# design.net
KiCad netlist of a schematic drawn in Altium Designer
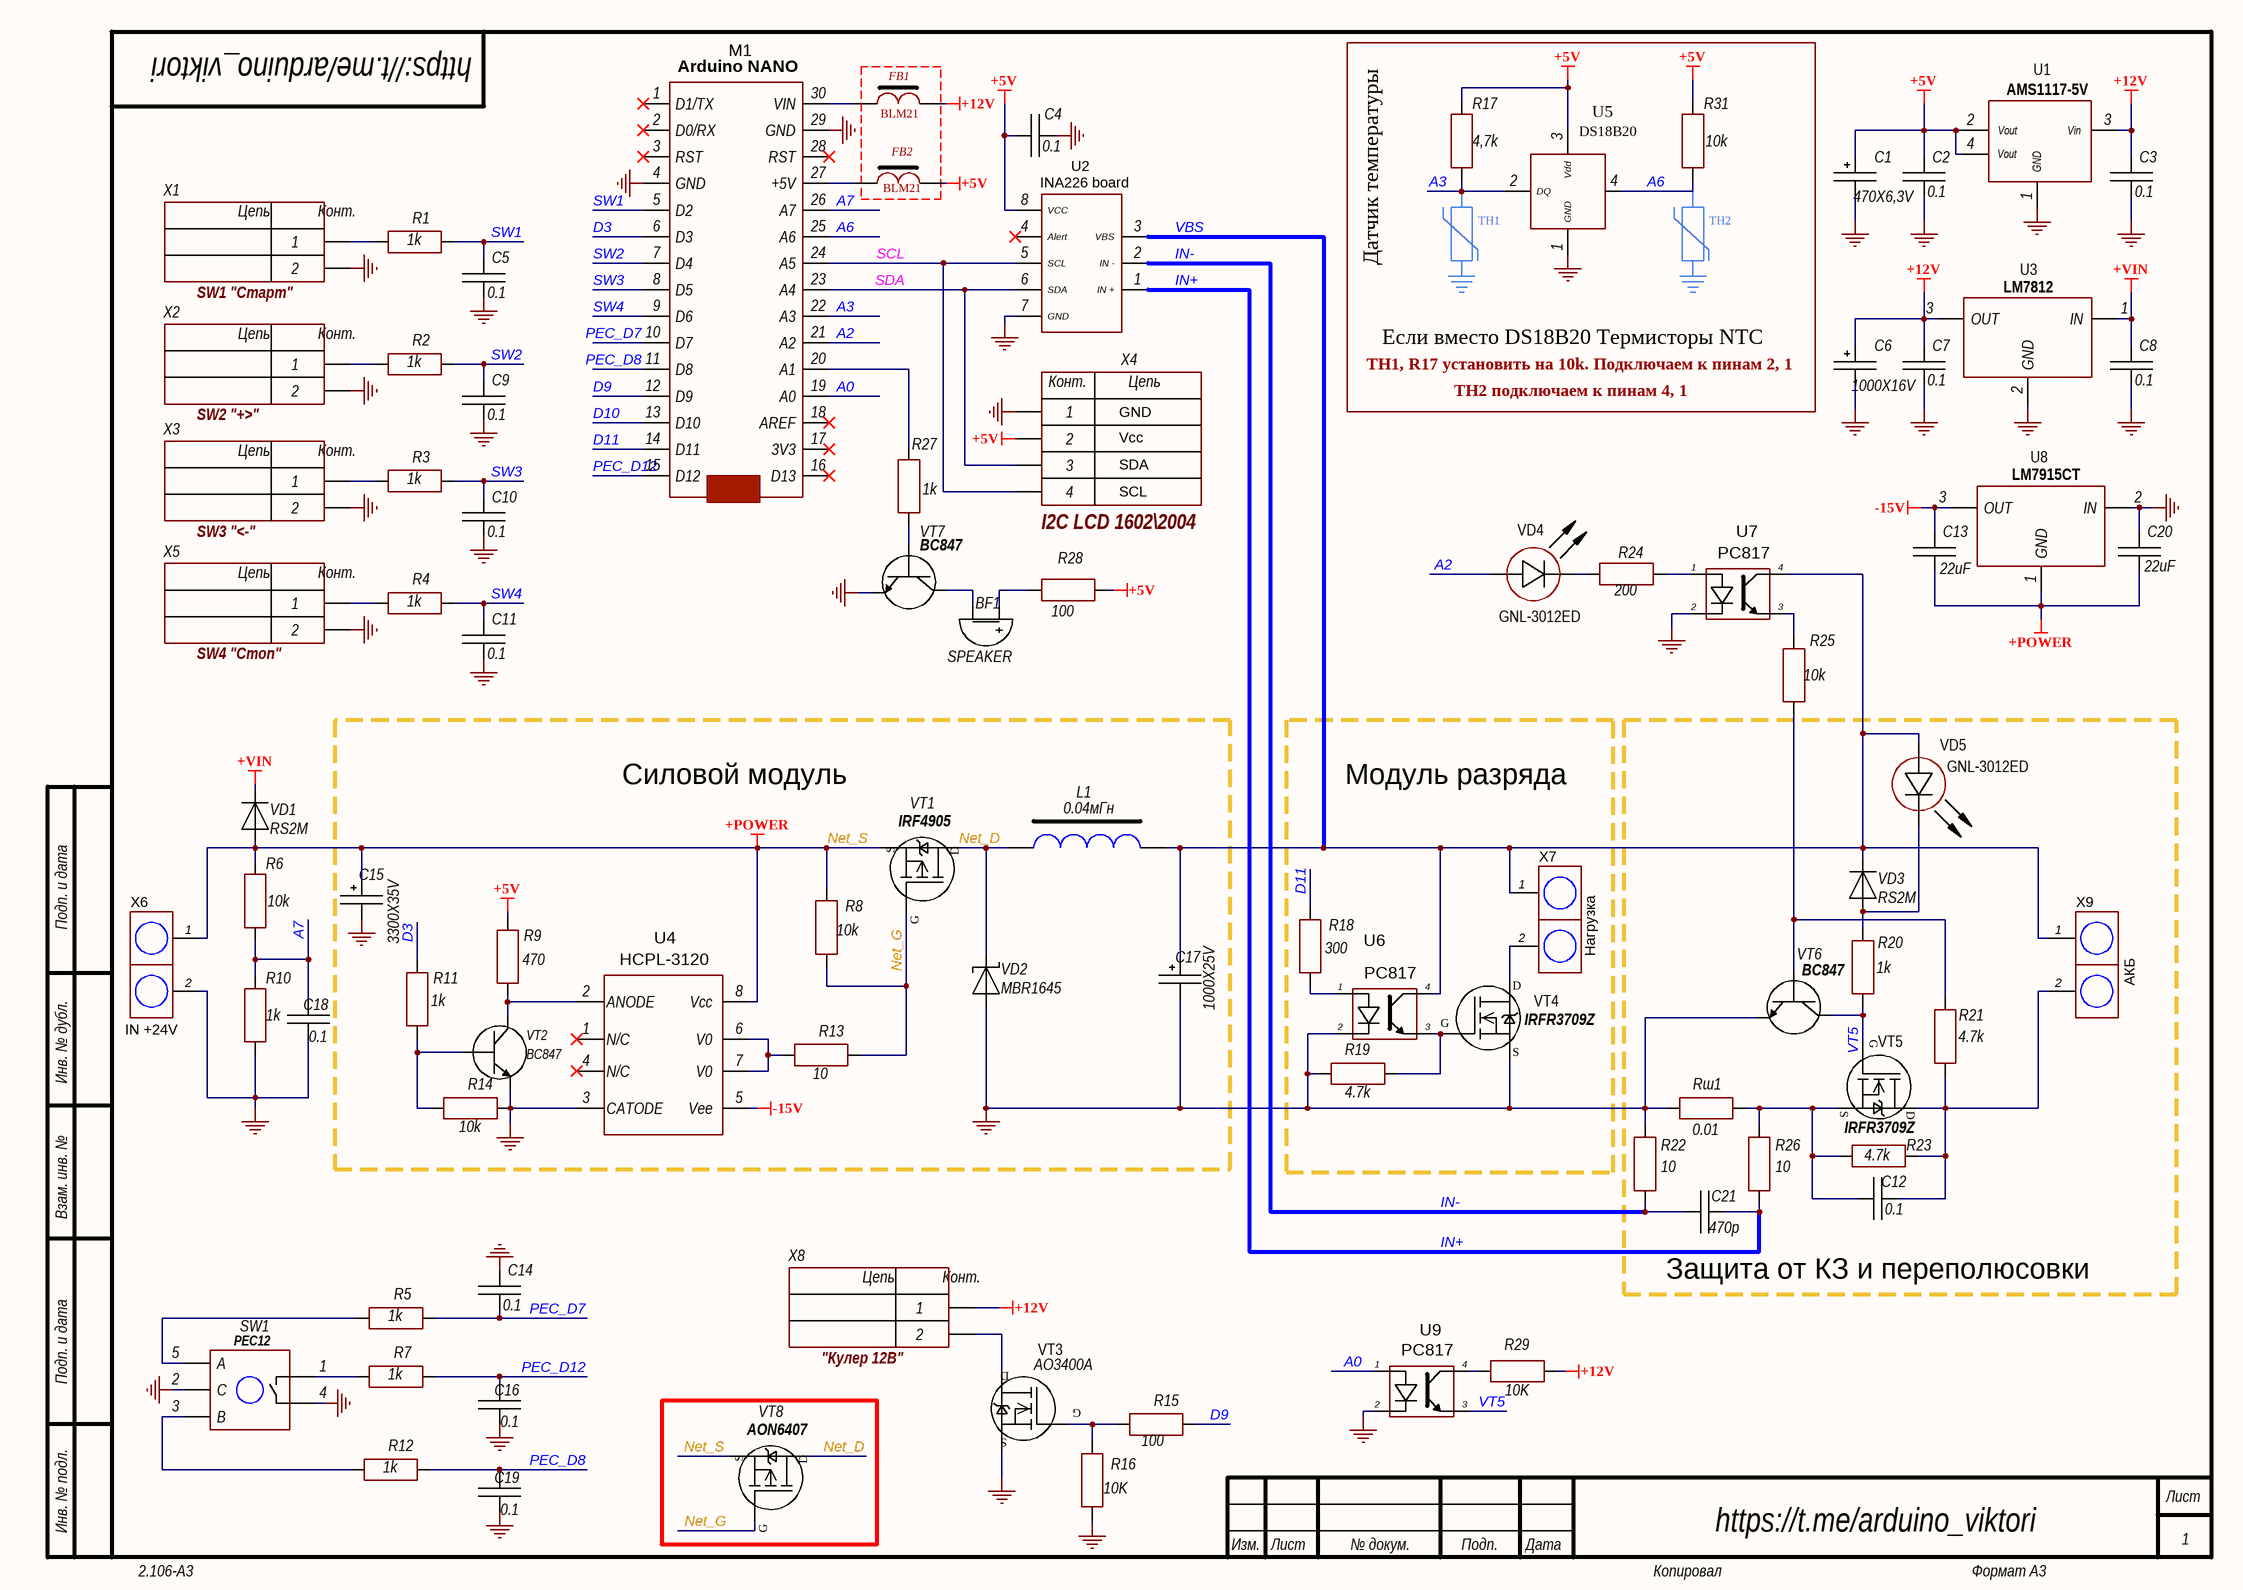
[diagram p0: Схема ЗУ.SchDoc]

(export (version "E")
  (design (tool "Eeschema 10.0.6"))
  (components
    (comp (ref "BF1")
      (value "SPEAKER")
      (footprint "CON: CWF-2")
      (fields (field (name "MANUFACTURER") "PUI Audio, Inc."))
      (libsource (lib "Discrete") (part "Buzzer"))
    )
    (comp (ref "C1")
      (value "470X6,3V")
      (footprint "standard:D8C3.5H12")
      (libsource (lib "Discrete") (part "AlumCap"))
    )
    (comp (ref "C2")
      (value "0.1")
      (footprint "standard:CH0805C")
      (libsource (lib "Discrete") (part "Capacitor"))
    )
    (comp (ref "C3")
      (value "0.1")
      (footprint "standard:CH0805C")
      (libsource (lib "Discrete") (part "Capacitor"))
    )
    (comp (ref "C4")
      (value "0.1")
      (footprint "standard:CH0805C")
      (libsource (lib "Discrete") (part "Capacitor"))
    )
    (comp (ref "C5")
      (value "0.1")
      (footprint "standard:CH0805C")
      (libsource (lib "Discrete") (part "Capacitor"))
    )
    (comp (ref "C6")
      (value "1000X16V")
      (footprint "standard:D10C5H20")
      (libsource (lib "Discrete") (part "AlumCap"))
    )
    (comp (ref "C7")
      (value "0.1")
      (footprint "standard:CH0805C")
      (libsource (lib "Discrete") (part "Capacitor"))
    )
    (comp (ref "C8")
      (value "0.1")
      (footprint "standard:CH0805C")
      (libsource (lib "Discrete") (part "Capacitor"))
    )
    (comp (ref "C9")
      (value "0.1")
      (footprint "standard:CH0805C")
      (libsource (lib "Discrete") (part "Capacitor"))
    )
    (comp (ref "C10")
      (value "0.1")
      (footprint "standard:CH0805C")
      (libsource (lib "Discrete") (part "Capacitor"))
    )
    (comp (ref "C11")
      (value "0.1")
      (footprint "standard:CH0805C")
      (libsource (lib "Discrete") (part "Capacitor"))
    )
    (comp (ref "C12")
      (value "0.1")
      (footprint "standard:CH0805C")
      (libsource (lib "Discrete") (part "Capacitor"))
    )
    (comp (ref "C13")
      (value "22uF")
      (footprint "standard:CH1206C")
      (libsource (lib "Discrete") (part "Capacitor"))
    )
    (comp (ref "C14")
      (value "0.1")
      (footprint "standard:CH0805C")
      (libsource (lib "Discrete") (part "Capacitor"))
    )
    (comp (ref "C15")
      (value "3300X35V")
      (footprint "standard:D16C7.5H25")
      (libsource (lib "Discrete") (part "AlumCap"))
    )
    (comp (ref "C16")
      (value "0.1")
      (footprint "standard:CH0805C")
      (libsource (lib "Discrete") (part "Capacitor"))
    )
    (comp (ref "C17")
      (value "1000X25V")
      (footprint "standard:D10C5H20")
      (libsource (lib "Discrete") (part "AlumCap"))
    )
    (comp (ref "C18")
      (value "0.1")
      (footprint "standard:CH0805C")
      (libsource (lib "Discrete") (part "Capacitor"))
    )
    (comp (ref "C19")
      (value "0.1")
      (footprint "standard:CH0805C")
      (libsource (lib "Discrete") (part "Capacitor"))
    )
    (comp (ref "C20")
      (value "22uF")
      (footprint "standard:CH1206C")
      (libsource (lib "Discrete") (part "Capacitor"))
    )
    (comp (ref "C21")
      (value "470p")
      (footprint "standard:CH0805C")
      (libsource (lib "Discrete") (part "Capacitor"))
    )
    (comp (ref "FB1") (value "BLM21") (footprint "CH0805L") (libsource (lib "Discrete") (part "FB-1")))
    (comp (ref "FB2") (value "BLM21") (footprint "CH0805L") (libsource (lib "Discrete") (part "FB-1")))
    (comp (ref "L1") (value "0.04мГн") (footprint "POWER_L") (libsource (lib "Transformers") (part "TRANS")))
    (comp (ref "M1")
      (value "Arduino NANO")
      (footprint "ARDUINO NANA")
      (libsource (lib "Module") (part "Arduino nano"))
    )
    (comp (ref "R1") (value "1k") (footprint "standard:CH0805R") (libsource (lib "") (part "Resistor_2")))
    (comp (ref "R2") (value "1k") (footprint "standard:CH0805R") (libsource (lib "") (part "Resistor_2")))
    (comp (ref "R3") (value "1k") (footprint "standard:CH0805R") (libsource (lib "") (part "Resistor_2")))
    (comp (ref "R4") (value "1k") (footprint "standard:CH0805R") (libsource (lib "") (part "Resistor_2")))
    (comp (ref "R5") (value "1k") (footprint "standard:CH0805R") (libsource (lib "") (part "Resistor_2")))
    (comp (ref "R6")
      (value "10k")
      (footprint "standard:CH0805R")
      (libsource (lib "Discrete") (part "Resistor"))
    )
    (comp (ref "R7") (value "1k") (footprint "standard:CH0805R") (libsource (lib "") (part "Resistor_2")))
    (comp (ref "R8")
      (value "10k")
      (footprint "standard:CH0805R")
      (libsource (lib "Discrete") (part "Resistor"))
    )
    (comp (ref "R9")
      (value "470")
      (footprint "standard:CH0805R")
      (libsource (lib "Discrete") (part "Resistor"))
    )
    (comp (ref "R10")
      (value "1k")
      (footprint "standard:CH0805R")
      (libsource (lib "Discrete") (part "Resistor"))
    )
    (comp (ref "R11")
      (value "1k")
      (footprint "standard:CH0805R")
      (libsource (lib "Discrete") (part "Resistor"))
    )
    (comp (ref "R12") (value "1k") (footprint "standard:CH0805R") (libsource (lib "") (part "Resistor_2")))
    (comp (ref "R13") (value "10") (footprint "standard:CH0805R") (libsource (lib "") (part "Resistor_2")))
    (comp (ref "R14") (value "10k") (footprint "standard:CH0805R") (libsource (lib "") (part "Resistor_2")))
    (comp (ref "R15") (value "100") (footprint "standard:CH0805R") (libsource (lib "") (part "Resistor_2")))
    (comp (ref "R16")
      (value "10K")
      (footprint "standard:CH0805R")
      (libsource (lib "Discrete") (part "Resistor"))
    )
    (comp (ref "R17")
      (value "4,7k")
      (footprint "standard:CH0805R")
      (libsource (lib "Discrete") (part "Resistor"))
    )
    (comp (ref "R18")
      (value "300")
      (footprint "standard:CH0805R")
      (libsource (lib "Discrete") (part "Resistor"))
    )
    (comp (ref "R19") (value "4.7k") (footprint "standard:CH0805R") (libsource (lib "") (part "Resistor_4")))
    (comp (ref "R20") (value "1k") (footprint "standard:CH0805R") (libsource (lib "") (part "Resistor_1")))
    (comp (ref "R21") (value "4.7k") (footprint "standard:CH0805R") (libsource (lib "") (part "Resistor_1")))
    (comp (ref "R22") (value "10") (footprint "standard:CH0805R") (libsource (lib "") (part "Resistor_1")))
    (comp (ref "R23") (value "4.7k") (footprint "standard:CH0805R") (libsource (lib "") (part "Resistor_3")))
    (comp (ref "R24") (value "200") (footprint "standard:CH0805R") (libsource (lib "") (part "Resistor_2")))
    (comp (ref "R25") (value "10k") (footprint "standard:CH0805R") (libsource (lib "") (part "Resistor_1")))
    (comp (ref "R26") (value "10") (footprint "standard:CH0805R") (libsource (lib "") (part "Resistor_1")))
    (comp (ref "R27")
      (value "1k")
      (footprint "standard:CH0805R")
      (libsource (lib "Discrete") (part "Resistor"))
    )
    (comp (ref "R28") (value "100") (footprint "standard:CH0805R") (libsource (lib "") (part "Resistor_3")))
    (comp (ref "R29") (value "10K") (footprint "standard:CH0805R") (libsource (lib "") (part "Resistor_3")))
    (comp (ref "R31")
      (value "10k")
      (footprint "standard:CH0805R")
      (libsource (lib "Discrete") (part "Resistor"))
    )
    (comp (ref "Rш1") (value "0.01") (footprint "HUNT 10mm") (libsource (lib "") (part "Resistor_3")))
    (comp (ref "SW1")
      (value "PEC12")
      (footprint "CON: CWF-5")
      (description "Encoder")
      (libsource (lib "Connectors") (part "PEC12"))
    )
    (comp (ref "U1") (value "AMS1117-5V") (footprint "SOT223") (libsource (lib "Analog") (part "AMS117")))
    (comp (ref "U2")
      (value "INA226 board")
      (footprint "CON: PBS-8")
      (libsource (lib "Module") (part "INA226"))
    )
    (comp (ref "U3")
      (value "LM7812")
      (footprint "TO220_123")
      (libsource (lib "Power Supplies") (part "7809"))
    )
    (comp (ref "U4") (value "HCPL-3120") (footprint "DIP-8") (libsource (lib "Digital") (part "HCPL-3120")))
    (comp (ref "U5")
      (value "DS18B20")
      (footprint "CON: PLS-4")
      (libsource (lib "Module") (part "DS18B20_V1"))
    )
    (comp (ref "U6") (value "PC817") (footprint "PC817-SMD") (libsource (lib "") (part "PC817_1")))
    (comp (ref "U7") (value "PC817") (footprint "PC817-SMD") (libsource (lib "Discrete") (part "PC817")))
    (comp (ref "U8") (value "LM7915CT") (footprint "TO-220_90") (libsource (lib "") (part "7809_1")))
    (comp (ref "U9") (value "PC817") (footprint "PC817-SMD") (libsource (lib "Discrete") (part "PC817")))
    (comp (ref "VD1") (value "RS2M") (footprint "standard:SMB") (libsource (lib "Diods") (part "Diod")))
    (comp (ref "VD2")
      (value "MBR1645")
      (footprint "TO-220_2pin")
      (libsource (lib "Diods") (part "Diod Schottky"))
    )
    (comp (ref "VD3") (value "RS2M") (footprint "standard:SMB") (libsource (lib "Diods") (part "Diod")))
    (comp (ref "VD4")
      (value "GNL-3012ED")
      (footprint "DIOD: LED5MM_R")
      (libsource (lib "Diods") (part "LED"))
    )
    (comp (ref "VD5")
      (value "GNL-3012ED")
      (footprint "DIOD: LED5MM_R")
      (libsource (lib "Diods") (part "LED"))
    )
    (comp (ref "VT1")
      (value "IRF4905")
      (footprint "TO220_123_V")
      (libsource (lib "Transistor") (part "P-KANAL"))
    )
    (comp (ref "VT2") (value "BC847") (footprint "SOT23_123") (libsource (lib "Transistor") (part "N-P-N")))
    (comp (ref "VT3") (value "AO3400A") (footprint "SOT23_132") (libsource (lib "") (part "N-KANAL_1")))
    (comp (ref "VT4") (value "IRFR3709Z") (footprint "D2PAK") (libsource (lib "Transistor") (part "N-KANAL")))
    (comp (ref "VT5") (value "IRFR3709Z") (footprint "D2PAK") (libsource (lib "Transistor") (part "N-KANAL")))
    (comp (ref "VT6") (value "BC847") (footprint "SOT23_123") (libsource (lib "Transistor") (part "N-P-N")))
    (comp (ref "VT7") (value "BC847") (footprint "SOT23_123") (libsource (lib "Transistor") (part "N-P-N")))
    (comp (ref "VT8") (value "AON6407") (footprint "DFN5x6") (libsource (lib "Transistor") (part "P-KANAL")))
    (comp (ref "X1")
      (value "SW1 \"Старт\"")
      (footprint "custom:CON: CWF-2")
      (libsource (lib "Connectors") (part "2-Connector"))
    )
    (comp (ref "X2")
      (value "SW2 \"+>\"")
      (footprint "custom:CON: CWF-2")
      (libsource (lib "Connectors") (part "2-Connector"))
    )
    (comp (ref "X3")
      (value "SW3 \"<-\"")
      (footprint "custom:CON: CWF-2")
      (libsource (lib "Connectors") (part "2-Connector"))
    )
    (comp (ref "X4")
      (value "I2C LCD 160~{2}2004")
      (footprint "custom:CON: CWF-4")
      (libsource (lib "Connectors") (part "4-Connector"))
    )
    (comp (ref "X5")
      (value "SW4 \"Стоп\"")
      (footprint "custom:CON: CWF-2")
      (libsource (lib "Connectors") (part "2-Connector"))
    )
    (comp (ref "X6")
      (value "IN +24V")
      (footprint "CON: 2P_5mm")
      (libsource (lib "Connectors") (part "2-CON"))
    )
    (comp (ref "X7") (value "Нагрузка") (footprint "CON: 2P_5mm") (libsource (lib "") (part "2-CON_1")))
    (comp (ref "X8")
      (value "\"Кулер 12В\"")
      (footprint "custom:CON: CWF-2")
      (libsource (lib "Connectors") (part "2-Connector"))
    )
    (comp (ref "X9") (value "АКБ") (footprint "CON: 2P_5mm") (libsource (lib "") (part "2-CON_1")))
  )
  (nets
    (net (code "1") (name "+5V") (class "Default")
      (node (ref "C1") (pin "1") (pinfunction "1_1") (pintype "power_in"))
      (node (ref "C2") (pin "1") (pinfunction "1_1") (pintype "passive"))
      (node (ref "C4") (pin "2") (pinfunction "2_2") (pintype "passive"))
      (node (ref "FB2") (pin "2") (pinfunction "2_2") (pintype "passive"))
      (node (ref "R17") (pin "2") (pinfunction "2_2") (pintype "passive"))
      (node (ref "R28") (pin "1") (pinfunction "1_1") (pintype "passive"))
      (node (ref "R31") (pin "2") (pinfunction "2_2") (pintype "passive"))
      (node (ref "R9") (pin "2") (pinfunction "2_2") (pintype "passive"))
      (node (ref "U1") (pin "2") (pinfunction "Vout_2") (pintype "passive"))
      (node (ref "U1") (pin "4") (pinfunction "Vout_4") (pintype "passive"))
      (node (ref "U2") (pin "8") (pinfunction "VCC_8") (pintype "passive"))
      (node (ref "U5") (pin "3") (pinfunction "Vdd_3") (pintype "passive"))
      (node (ref "X4") (pin "2") (pinfunction "2_2") (pintype "passive"))
    )
    (net (code "2") (name "+12V") (class "Default")
      (node (ref "C3") (pin "1") (pinfunction "1_1") (pintype "passive"))
      (node (ref "C6") (pin "1") (pinfunction "1_1") (pintype "power_in"))
      (node (ref "C7") (pin "1") (pinfunction "1_1") (pintype "passive"))
      (node (ref "FB1") (pin "2") (pinfunction "2_2") (pintype "passive"))
      (node (ref "R29") (pin "1") (pinfunction "1_1") (pintype "passive"))
      (node (ref "U1") (pin "3") (pinfunction "Vin_3") (pintype "passive"))
      (node (ref "U3") (pin "3") (pinfunction "OUT_3") (pintype "passive"))
      (node (ref "X8") (pin "1") (pinfunction "1_1") (pintype "passive"))
    )
    (net (code "3") (name "+POWER") (class "Default")
      (node (ref "C13") (pin "2") (pinfunction "2_2") (pintype "passive"))
      (node (ref "C15") (pin "1") (pinfunction "1_1") (pintype "power_in"))
      (node (ref "C20") (pin "2") (pinfunction "2_2") (pintype "passive"))
      (node (ref "R6") (pin "2") (pinfunction "2_2") (pintype "passive"))
      (node (ref "R8") (pin "2") (pinfunction "2_2") (pintype "passive"))
      (node (ref "U4") (pin "8") (pinfunction "Vcc_8") (pintype "passive"))
      (node (ref "U8") (pin "1") (pinfunction "GND_1") (pintype "passive"))
      (node (ref "VD1") (pin "1") (pinfunction "1_1") (pintype "passive"))
      (node (ref "VT1") (pin "3") (pinfunction "Исток_3") (pintype "passive"))
      (node (ref "VT8") (pin "3") (pinfunction "Исток_3") (pintype "passive"))
      (node (ref "X6") (pin "1") (pinfunction "1_1") (pintype "passive"))
    )
    (net (code "4") (name "+VIN") (class "Default")
      (node (ref "C8") (pin "1") (pinfunction "1_1") (pintype "passive"))
      (node (ref "U3") (pin "1") (pinfunction "IN_1") (pintype "power_in"))
      (node (ref "VD1") (pin "2") (pinfunction "2_2") (pintype "passive"))
    )
    (net (code "5") (name "-15V") (class "Default")
      (node (ref "C13") (pin "1") (pinfunction "1_1") (pintype "passive"))
      (node (ref "U4") (pin "5") (pinfunction "Vee_5") (pintype "passive"))
      (node (ref "U8") (pin "3") (pinfunction "OUT_3") (pintype "passive"))
    )
    (net (code "6") (name "/A0") (class "Default")
      (node (ref "M1") (pin "19") (pinfunction "A0_19") (pintype "passive"))
      (node (ref "U9") (pin "1") (pinfunction "1_1") (pintype "passive"))
    )
    (net (code "7") (name "/A2") (class "Default")
      (node (ref "M1") (pin "21") (pinfunction "A2_21") (pintype "passive"))
      (node (ref "VD4") (pin "1") (pinfunction "A_1") (pintype "passive"))
    )
    (net (code "8") (name "/A3") (class "Default")
      (node (ref "M1") (pin "22") (pinfunction "A3_22") (pintype "passive"))
      (node (ref "R17") (pin "1") (pinfunction "1_1") (pintype "passive"))
      (node (ref "U5") (pin "2") (pinfunction "DQ_2") (pintype "passive"))
    )
    (net (code "9") (name "/A6") (class "Default")
      (node (ref "M1") (pin "25") (pinfunction "A6_25") (pintype "passive"))
      (node (ref "R31") (pin "1") (pinfunction "1_1") (pintype "passive"))
      (node (ref "U5") (pin "4") (pinfunction "DQ_4") (pintype "passive"))
    )
    (net (code "10") (name "/A7") (class "Default")
      (node (ref "C18") (pin "1") (pinfunction "1_1") (pintype "passive"))
      (node (ref "M1") (pin "26") (pinfunction "A7_26") (pintype "passive"))
      (node (ref "R10") (pin "2") (pinfunction "2_2") (pintype "passive"))
      (node (ref "R6") (pin "1") (pinfunction "1_1") (pintype "passive"))
    )
    (net (code "11") (name "/D3") (class "Default")
      (node (ref "M1") (pin "6") (pinfunction "D3_6") (pintype "passive"))
      (node (ref "R11") (pin "2") (pinfunction "2_2") (pintype "passive"))
    )
    (net (code "12") (name "/D9") (class "Default")
      (node (ref "M1") (pin "12") (pinfunction "D9_12") (pintype "passive"))
      (node (ref "R15") (pin "2") (pinfunction "2_2") (pintype "passive"))
    )
    (net (code "13") (name "/D10") (class "Default")
      (node (ref "M1") (pin "13") (pinfunction "D10_13") (pintype "passive"))
    )
    (net (code "14") (name "/D11") (class "Default")
      (node (ref "M1") (pin "14") (pinfunction "D11_14") (pintype "passive"))
      (node (ref "R18") (pin "2") (pinfunction "2_2") (pintype "passive"))
    )
    (net (code "15") (name "/IN+") (class "Default")
      (node (ref "C21") (pin "1") (pinfunction "1_1") (pintype "passive"))
      (node (ref "R26") (pin "2") (pinfunction "2_2") (pintype "passive"))
      (node (ref "U2") (pin "1") (pinfunction "IN_+_1") (pintype "passive"))
    )
    (net (code "16") (name "/IN-") (class "Default")
      (node (ref "C21") (pin "2") (pinfunction "2_2") (pintype "passive"))
      (node (ref "R22") (pin "2") (pinfunction "2_2") (pintype "passive"))
      (node (ref "U2") (pin "2") (pinfunction "IN_-_2") (pintype "passive"))
    )
    (net (code "17") (name "/Net_D") (class "Default")
      (node (ref "L1") (pin "1") (pinfunction "1_1") (pintype "power_in"))
      (node (ref "VD2") (pin "1") (pinfunction "1_1") (pintype "passive"))
      (node (ref "VT1") (pin "2") (pinfunction "Сток_2") (pintype "passive"))
      (node (ref "VT8") (pin "2") (pinfunction "Сток_2") (pintype "passive"))
    )
    (net (code "18") (name "/Net_G") (class "Default")
      (node (ref "R13") (pin "2") (pinfunction "2_2") (pintype "passive"))
      (node (ref "R8") (pin "1") (pinfunction "1_1") (pintype "passive"))
      (node (ref "VT1") (pin "1") (pinfunction "Затвор(Gate)_1") (pintype "passive"))
      (node (ref "VT8") (pin "1") (pinfunction "Затвор(Gate)_1") (pintype "passive"))
    )
    (net (code "19") (name "/PEC_D7") (class "Default")
      (node (ref "C14") (pin "1") (pinfunction "1_1") (pintype "passive"))
      (node (ref "M1") (pin "10") (pinfunction "D7_10") (pintype "passive"))
      (node (ref "R5") (pin "2") (pinfunction "2_2") (pintype "passive"))
    )
    (net (code "20") (name "/PEC_D8") (class "Default")
      (node (ref "C19") (pin "1") (pinfunction "1_1") (pintype "passive"))
      (node (ref "M1") (pin "11") (pinfunction "D8_11") (pintype "passive"))
      (node (ref "R12") (pin "2") (pinfunction "2_2") (pintype "passive"))
    )
    (net (code "21") (name "/PEC_D12") (class "Default")
      (node (ref "C16") (pin "1") (pinfunction "1_1") (pintype "passive"))
      (node (ref "M1") (pin "15") (pinfunction "D12_15") (pintype "passive"))
      (node (ref "R7") (pin "2") (pinfunction "2_2") (pintype "passive"))
    )
    (net (code "22") (name "/SCL") (class "Default")
      (node (ref "M1") (pin "24") (pinfunction "A5_24") (pintype "passive"))
      (node (ref "U2") (pin "5") (pinfunction "SCL_5") (pintype "passive"))
      (node (ref "X4") (pin "4") (pinfunction "4_4") (pintype "power_in"))
    )
    (net (code "23") (name "/SDA") (class "Default")
      (node (ref "M1") (pin "23") (pinfunction "A4_23") (pintype "passive"))
      (node (ref "U2") (pin "6") (pinfunction "SDA_6") (pintype "passive"))
      (node (ref "X4") (pin "3") (pinfunction "3_3") (pintype "power_in"))
    )
    (net (code "24") (name "/SW1") (class "Default")
      (node (ref "C5") (pin "2") (pinfunction "2_2") (pintype "passive"))
      (node (ref "M1") (pin "5") (pinfunction "D2_5") (pintype "passive"))
      (node (ref "R1") (pin "2") (pinfunction "2_2") (pintype "passive"))
    )
    (net (code "25") (name "/SW2") (class "Default")
      (node (ref "C9") (pin "2") (pinfunction "2_2") (pintype "passive"))
      (node (ref "M1") (pin "7") (pinfunction "D4_7") (pintype "passive"))
      (node (ref "R2") (pin "2") (pinfunction "2_2") (pintype "passive"))
    )
    (net (code "26") (name "/SW3") (class "Default")
      (node (ref "C10") (pin "2") (pinfunction "2_2") (pintype "passive"))
      (node (ref "M1") (pin "8") (pinfunction "D5_8") (pintype "passive"))
      (node (ref "R3") (pin "2") (pinfunction "2_2") (pintype "passive"))
    )
    (net (code "27") (name "/SW4") (class "Default")
      (node (ref "C11") (pin "2") (pinfunction "2_2") (pintype "passive"))
      (node (ref "M1") (pin "9") (pinfunction "D6_9") (pintype "passive"))
      (node (ref "R4") (pin "2") (pinfunction "2_2") (pintype "passive"))
    )
    (net (code "28") (name "/VBS") (class "Default")
      (node (ref "C17") (pin "1") (pinfunction "1_1") (pintype "power_in"))
      (node (ref "L1") (pin "2") (pinfunction "2_2") (pintype "power_in"))
      (node (ref "U2") (pin "3") (pinfunction "VBS_3") (pintype "passive"))
      (node (ref "U6") (pin "4") (pinfunction "4_4") (pintype "passive"))
      (node (ref "U7") (pin "4") (pinfunction "4_4") (pintype "passive"))
      (node (ref "VD3") (pin "2") (pinfunction "2_2") (pintype "passive"))
      (node (ref "VD5") (pin "1") (pinfunction "A_1") (pintype "passive"))
      (node (ref "X7") (pin "1") (pinfunction "1_1") (pintype "passive"))
      (node (ref "X9") (pin "1") (pinfunction "1_1") (pintype "passive"))
    )
    (net (code "29") (name "/VT5") (class "Default")
      (node (ref "R20") (pin "2") (pinfunction "2_2") (pintype "passive"))
      (node (ref "U9") (pin "3") (pinfunction "3_3") (pintype "passive"))
      (node (ref "VT5") (pin "1") (pinfunction "Затвор_1") (pintype "passive"))
      (node (ref "VT6") (pin "2") (pinfunction "C_2") (pintype "passive"))
    )
    (net (code "30") (name "GND") (class "Default")
      (node (ref "C1") (pin "2") (pinfunction "2_2") (pintype "power_in"))
      (node (ref "C10") (pin "1") (pinfunction "1_1") (pintype "passive"))
      (node (ref "C11") (pin "1") (pinfunction "1_1") (pintype "passive"))
      (node (ref "C14") (pin "2") (pinfunction "2_2") (pintype "passive"))
      (node (ref "C15") (pin "2") (pinfunction "2_2") (pintype "power_in"))
      (node (ref "C16") (pin "2") (pinfunction "2_2") (pintype "passive"))
      (node (ref "C17") (pin "2") (pinfunction "2_2") (pintype "power_in"))
      (node (ref "C18") (pin "2") (pinfunction "2_2") (pintype "passive"))
      (node (ref "C19") (pin "2") (pinfunction "2_2") (pintype "passive"))
      (node (ref "C2") (pin "2") (pinfunction "2_2") (pintype "passive"))
      (node (ref "C20") (pin "1") (pinfunction "1_1") (pintype "passive"))
      (node (ref "C3") (pin "2") (pinfunction "2_2") (pintype "passive"))
      (node (ref "C4") (pin "1") (pinfunction "1_1") (pintype "passive"))
      (node (ref "C5") (pin "1") (pinfunction "1_1") (pintype "passive"))
      (node (ref "C6") (pin "2") (pinfunction "2_2") (pintype "power_in"))
      (node (ref "C7") (pin "2") (pinfunction "2_2") (pintype "passive"))
      (node (ref "C8") (pin "2") (pinfunction "2_2") (pintype "passive"))
      (node (ref "C9") (pin "1") (pinfunction "1_1") (pintype "passive"))
      (node (ref "M1") (pin "29") (pinfunction "GND_29") (pintype "passive"))
      (node (ref "M1") (pin "4") (pinfunction "GND_4") (pintype "passive"))
      (node (ref "R10") (pin "1") (pinfunction "1_1") (pintype "passive"))
      (node (ref "R14") (pin "2") (pinfunction "2_2") (pintype "passive"))
      (node (ref "R16") (pin "1") (pinfunction "1_1") (pintype "passive"))
      (node (ref "R19") (pin "2") (pinfunction "2_2") (pintype "passive"))
      (node (ref "R22") (pin "1") (pinfunction "1_1") (pintype "passive"))
      (node (ref "Rш1") (pin "2") (pinfunction "2_2") (pintype "passive"))
      (node (ref "SW1") (pin "2") (pinfunction "C_2") (pintype "passive"))
      (node (ref "SW1") (pin "4") (pinfunction "4_4") (pintype "passive"))
      (node (ref "U1") (pin "1") (pinfunction "GND_1") (pintype "passive"))
      (node (ref "U2") (pin "7") (pinfunction "GND_7") (pintype "passive"))
      (node (ref "U3") (pin "2") (pinfunction "GND_2") (pintype "passive"))
      (node (ref "U4") (pin "3") (pinfunction "CATODE_3") (pintype "passive"))
      (node (ref "U5") (pin "1") (pinfunction "GND_1") (pintype "passive"))
      (node (ref "U6") (pin "2") (pinfunction "2_2") (pintype "passive"))
      (node (ref "U7") (pin "2") (pinfunction "2_2") (pintype "passive"))
      (node (ref "U8") (pin "2") (pinfunction "IN_2") (pintype "power_in"))
      (node (ref "U9") (pin "2") (pinfunction "2_2") (pintype "passive"))
      (node (ref "VD2") (pin "2") (pinfunction "2_2") (pintype "passive"))
      (node (ref "VT2") (pin "3") (pinfunction "E_3") (pintype "passive"))
      (node (ref "VT3") (pin "2") (pinfunction "Исток_2") (pintype "passive"))
      (node (ref "VT4") (pin "3") (pinfunction "Исток_3") (pintype "passive"))
      (node (ref "VT6") (pin "3") (pinfunction "E_3") (pintype "passive"))
      (node (ref "VT7") (pin "3") (pinfunction "E_3") (pintype "passive"))
      (node (ref "X1") (pin "2") (pinfunction "2_2") (pintype "passive"))
      (node (ref "X2") (pin "2") (pinfunction "2_2") (pintype "passive"))
      (node (ref "X3") (pin "2") (pinfunction "2_2") (pintype "passive"))
      (node (ref "X4") (pin "1") (pinfunction "1_1") (pintype "passive"))
      (node (ref "X5") (pin "2") (pinfunction "2_2") (pintype "passive"))
      (node (ref "X6") (pin "2") (pinfunction "2_2") (pintype "passive"))
    )
    (net (code "31") (name "Net-(BF1-+)") (class "Default")
      (node (ref "BF1") (pin "1") (pinfunction "+_1") (pintype "passive"))
      (node (ref "R28") (pin "2") (pinfunction "2_2") (pintype "passive"))
    )
    (net (code "32") (name "Net-(BF1--)") (class "Default")
      (node (ref "BF1") (pin "2") (pinfunction "-_2") (pintype "passive"))
      (node (ref "VT7") (pin "2") (pinfunction "C_2") (pintype "passive"))
    )
    (net (code "33") (name "Net-(M1-+5V)") (class "Default")
      (node (ref "FB2") (pin "1") (pinfunction "1_1") (pintype "passive"))
      (node (ref "M1") (pin "27") (pinfunction "+5V_27") (pintype "passive"))
    )
    (net (code "34") (name "Net-(M1-A1)") (class "Default")
      (node (ref "M1") (pin "20") (pinfunction "A1_20") (pintype "passive"))
      (node (ref "R27") (pin "2") (pinfunction "2_2") (pintype "passive"))
    )
    (net (code "35") (name "Net-(M1-VIN)") (class "Default")
      (node (ref "FB1") (pin "1") (pinfunction "1_1") (pintype "passive"))
      (node (ref "M1") (pin "30") (pinfunction "VIN_30") (pintype "passive"))
    )
    (net (code "36") (name "Net-(R1-Pad1)") (class "Default")
      (node (ref "R1") (pin "1") (pinfunction "1_1") (pintype "passive"))
      (node (ref "X1") (pin "1") (pinfunction "1_1") (pintype "passive"))
    )
    (net (code "37") (name "Net-(R2-Pad1)") (class "Default")
      (node (ref "R2") (pin "1") (pinfunction "1_1") (pintype "passive"))
      (node (ref "X2") (pin "1") (pinfunction "1_1") (pintype "passive"))
    )
    (net (code "38") (name "Net-(R3-Pad1)") (class "Default")
      (node (ref "R3") (pin "1") (pinfunction "1_1") (pintype "passive"))
      (node (ref "X3") (pin "1") (pinfunction "1_1") (pintype "passive"))
    )
    (net (code "39") (name "Net-(R4-Pad1)") (class "Default")
      (node (ref "R4") (pin "1") (pinfunction "1_1") (pintype "passive"))
      (node (ref "X5") (pin "1") (pinfunction "1_1") (pintype "passive"))
    )
    (net (code "40") (name "Net-(R7-Pad1)") (class "Default")
      (node (ref "R7") (pin "1") (pinfunction "1_1") (pintype "passive"))
      (node (ref "SW1") (pin "1") (pinfunction "1_1") (pintype "passive"))
    )
    (net (code "41") (name "Net-(R13-Pad1)") (class "Default")
      (node (ref "R13") (pin "1") (pinfunction "1_1") (pintype "passive"))
      (node (ref "U4") (pin "6") (pinfunction "V0_6") (pintype "passive"))
      (node (ref "U4") (pin "7") (pinfunction "V0_7") (pintype "passive"))
    )
    (net (code "42") (name "Net-(R18-Pad1)") (class "Default")
      (node (ref "R18") (pin "1") (pinfunction "1_1") (pintype "passive"))
      (node (ref "U6") (pin "1") (pinfunction "1_1") (pintype "passive"))
    )
    (net (code "43") (name "Net-(R24-Pad2)") (class "Default")
      (node (ref "R24") (pin "2") (pinfunction "2_2") (pintype "passive"))
      (node (ref "U7") (pin "1") (pinfunction "1_1") (pintype "passive"))
    )
    (net (code "44") (name "Net-(R25-Pad1)") (class "Default")
      (node (ref "R25") (pin "1") (pinfunction "1_1") (pintype "passive"))
      (node (ref "U7") (pin "3") (pinfunction "3_3") (pintype "passive"))
    )
    (net (code "45") (name "Net-(R29-Pad2)") (class "Default")
      (node (ref "R29") (pin "2") (pinfunction "2_2") (pintype "passive"))
      (node (ref "U9") (pin "4") (pinfunction "4_4") (pintype "passive"))
    )
    (net (code "46") (name "Net-(SW1-A)") (class "Default")
      (node (ref "R5") (pin "1") (pinfunction "1_1") (pintype "passive"))
      (node (ref "SW1") (pin "5") (pinfunction "A_5") (pintype "passive"))
    )
    (net (code "47") (name "Net-(SW1-B)") (class "Default")
      (node (ref "R12") (pin "1") (pinfunction "1_1") (pintype "passive"))
      (node (ref "SW1") (pin "3") (pinfunction "B_3") (pintype "passive"))
    )
    (net (code "48") (name "Net-(U4-ANODE)") (class "Default")
      (node (ref "R9") (pin "1") (pinfunction "1_1") (pintype "passive"))
      (node (ref "U4") (pin "2") (pinfunction "ANODE_2") (pintype "passive"))
      (node (ref "VT2") (pin "2") (pinfunction "C_2") (pintype "passive"))
    )
    (net (code "49") (name "Net-(VD4-C)") (class "Default")
      (node (ref "R24") (pin "1") (pinfunction "1_1") (pintype "passive"))
      (node (ref "VD4") (pin "2") (pinfunction "C_2") (pintype "passive"))
    )
    (net (code "50") (name "Net-(VD5-C)") (class "Default")
      (node (ref "R20") (pin "1") (pinfunction "1_1") (pintype "passive"))
      (node (ref "VD3") (pin "1") (pinfunction "1_1") (pintype "passive"))
      (node (ref "VD5") (pin "2") (pinfunction "C_2") (pintype "passive"))
    )
    (net (code "51") (name "Net-(VT2-B)") (class "Default")
      (node (ref "R11") (pin "1") (pinfunction "1_1") (pintype "passive"))
      (node (ref "R14") (pin "1") (pinfunction "1_1") (pintype "passive"))
      (node (ref "VT2") (pin "1") (pinfunction "B_1") (pintype "passive"))
    )
    (net (code "52") (name "Net-(VT3-Затвор)") (class "Default")
      (node (ref "R15") (pin "1") (pinfunction "1_1") (pintype "passive"))
      (node (ref "R16") (pin "2") (pinfunction "2_2") (pintype "passive"))
      (node (ref "VT3") (pin "1") (pinfunction "Затвор_1") (pintype "passive"))
    )
    (net (code "53") (name "Net-(VT3-Сток)") (class "Default")
      (node (ref "VT3") (pin "3") (pinfunction "Сток_3") (pintype "passive"))
      (node (ref "X8") (pin "2") (pinfunction "2_2") (pintype "passive"))
    )
    (net (code "54") (name "Net-(VT4-Затвор)") (class "Default")
      (node (ref "R19") (pin "1") (pinfunction "1_1") (pintype "passive"))
      (node (ref "U6") (pin "3") (pinfunction "3_3") (pintype "passive"))
      (node (ref "VT4") (pin "1") (pinfunction "Затвор_1") (pintype "passive"))
    )
    (net (code "55") (name "Net-(VT4-Сток)") (class "Default")
      (node (ref "VT4") (pin "2") (pinfunction "Сток_2") (pintype "passive"))
      (node (ref "X7") (pin "2") (pinfunction "2_2") (pintype "passive"))
    )
    (net (code "56") (name "Net-(VT5-Исток)") (class "Default")
      (node (ref "C12") (pin "1") (pinfunction "1_1") (pintype "passive"))
      (node (ref "R23") (pin "2") (pinfunction "2_2") (pintype "passive"))
      (node (ref "R26") (pin "1") (pinfunction "1_1") (pintype "passive"))
      (node (ref "Rш1") (pin "1") (pinfunction "1_1") (pintype "passive"))
      (node (ref "VT5") (pin "3") (pinfunction "Исток_3") (pintype "passive"))
    )
    (net (code "57") (name "Net-(VT5-Сток)") (class "Default")
      (node (ref "C12") (pin "2") (pinfunction "2_2") (pintype "passive"))
      (node (ref "R21") (pin "2") (pinfunction "2_2") (pintype "passive"))
      (node (ref "R23") (pin "1") (pinfunction "1_1") (pintype "passive"))
      (node (ref "VT5") (pin "2") (pinfunction "Сток_2") (pintype "passive"))
      (node (ref "X9") (pin "2") (pinfunction "2_2") (pintype "passive"))
    )
    (net (code "58") (name "Net-(VT6-B)") (class "Default")
      (node (ref "R21") (pin "1") (pinfunction "1_1") (pintype "passive"))
      (node (ref "R25") (pin "2") (pinfunction "2_2") (pintype "passive"))
      (node (ref "VT6") (pin "1") (pinfunction "B_1") (pintype "passive"))
    )
    (net (code "59") (name "Net-(VT7-B)") (class "Default")
      (node (ref "R27") (pin "1") (pinfunction "1_1") (pintype "passive"))
      (node (ref "VT7") (pin "1") (pinfunction "B_1") (pintype "passive"))
    )
    (net (code "60") (name "unconnected-(M1-3V3-Pad17)") (class "Default")
      (node (ref "M1") (pin "17") (pinfunction "3V3_17") (pintype "passive+no_connect"))
    )
    (net (code "61") (name "unconnected-(M1-AREF-Pad18)") (class "Default")
      (node (ref "M1") (pin "18") (pinfunction "AREF_18") (pintype "passive+no_connect"))
    )
    (net (code "62") (name "unconnected-(M1-D0{slash}RX-Pad2)") (class "Default")
      (node (ref "M1") (pin "2") (pinfunction "D0/RX_2") (pintype "passive+no_connect"))
    )
    (net (code "63") (name "unconnected-(M1-D1{slash}TX-Pad1)") (class "Default")
      (node (ref "M1") (pin "1") (pinfunction "D1/TX_1") (pintype "passive+no_connect"))
    )
    (net (code "64") (name "unconnected-(M1-D13-Pad16)") (class "Default")
      (node (ref "M1") (pin "16") (pinfunction "D13_16") (pintype "passive+no_connect"))
    )
    (net (code "65") (name "unconnected-(M1-RST-Pad3)") (class "Default")
      (node (ref "M1") (pin "3") (pinfunction "RST_3") (pintype "passive+no_connect"))
    )
    (net (code "66") (name "unconnected-(M1-RST-Pad28)") (class "Default")
      (node (ref "M1") (pin "28") (pinfunction "RST_28") (pintype "passive+no_connect"))
    )
    (net (code "67") (name "unconnected-(U2-Alert-Pad4)") (class "Default")
      (node (ref "U2") (pin "4") (pinfunction "Alert_4") (pintype "passive+no_connect"))
    )
    (net (code "68") (name "unconnected-(U4-N{slash}C-Pad1)") (class "Default")
      (node (ref "U4") (pin "1") (pinfunction "N/C_1") (pintype "passive+no_connect"))
    )
    (net (code "69") (name "unconnected-(U4-N{slash}C-Pad4)") (class "Default")
      (node (ref "U4") (pin "4") (pinfunction "N/C_4") (pintype "passive+no_connect"))
    )
  )
)
